# 04_PWMDRIVER.net
KiCad netlist of a schematic drawn in Altium Designer
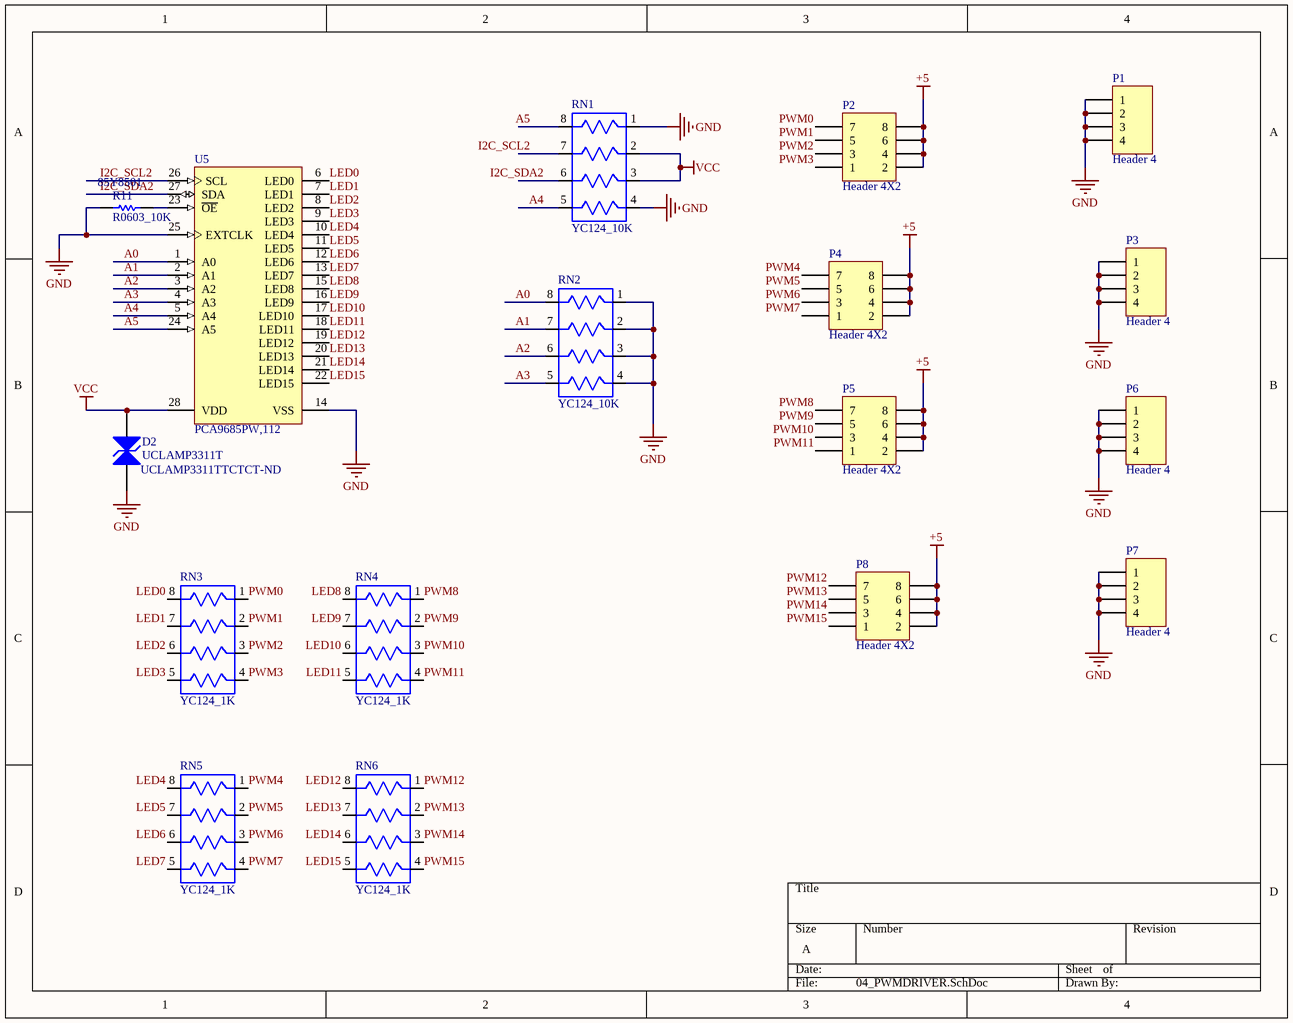
[diagram p0: 04_PWMDRIVER.SchDoc]

(export (version "E")
  (design (tool "Eeschema 10.0.6"))
  (components
    (comp (ref "D2")
      (value "UCLAMP3311T")
      (footprint "SEMT-SLP1006P2-2_V")
      (description "SEMTECH - UCLAMP3311T.TCT - TVS ARRAY, 40W, 3.3V, BI-DIRECTIONAL, SLP1006P2T")
      (fields
        (field (name "SUPPLIER PART NUMBER 1") "UCLAMP3311TTCTCT-ND")
        (field (name "MANUFACTURER") "Semtech")
        (field (name "MANUFACTURER PART NUMBER") "UCLAMP3311T.TCT")
      )
      (libsource (lib "RBS_library") (part "TVS_CLAMP"))
    )
    (comp (ref "P1")
      (value "Header 4")
      (footprint "HDR1X4")
      (description "Header, 4-Pin")
      (fields (field (name "PUBLISHER") "Altium Limited"))
      (libsource (lib "Miscellaneous Connectors") (part "Header 4"))
    )
    (comp (ref "P2")
      (value "Header 4X2")
      (footprint "HDR2X4")
      (description "Header, 4-Pin, Dual row")
      (fields (field (name "PUBLISHER") "Altium Limited"))
      (libsource (lib "Miscellaneous Connectors") (part "Header 4X2"))
    )
    (comp (ref "P3")
      (value "Header 4")
      (footprint "HDR1X4")
      (description "Header, 4-Pin")
      (fields (field (name "PUBLISHER") "Altium Limited"))
      (libsource (lib "Miscellaneous Connectors") (part "Header 4"))
    )
    (comp (ref "P4")
      (value "Header 4X2")
      (footprint "HDR2X4")
      (description "Header, 4-Pin, Dual row")
      (fields (field (name "PUBLISHER") "Altium Limited"))
      (libsource (lib "Miscellaneous Connectors") (part "Header 4X2"))
    )
    (comp (ref "P5")
      (value "Header 4X2")
      (footprint "HDR2X4")
      (description "Header, 4-Pin, Dual row")
      (fields (field (name "PUBLISHER") "Altium Limited"))
      (libsource (lib "Miscellaneous Connectors") (part "Header 4X2"))
    )
    (comp (ref "P6")
      (value "Header 4")
      (footprint "HDR1X4")
      (description "Header, 4-Pin")
      (fields (field (name "PUBLISHER") "Altium Limited"))
      (libsource (lib "Miscellaneous Connectors") (part "Header 4"))
    )
    (comp (ref "P7")
      (value "Header 4")
      (footprint "HDR1X4")
      (description "Header, 4-Pin")
      (fields (field (name "PUBLISHER") "Altium Limited"))
      (libsource (lib "Miscellaneous Connectors") (part "Header 4"))
    )
    (comp (ref "P8")
      (value "Header 4X2")
      (footprint "HDR2X4")
      (description "Header, 4-Pin, Dual row")
      (fields (field (name "PUBLISHER") "Altium Limited"))
      (libsource (lib "Miscellaneous Connectors") (part "Header 4X2"))
    )
    (comp (ref "R11")
      (value "R0603_10K")
      (footprint "RESC1609X55X30LL15T15")
      (description "PANASONIC - ERJ-3EKF1002V. - THICK FILM CHIP RES, 0603, 1%, PRECISION")
      (fields
        (field (name "SUPPLIER PART NUMBER 1") "85Y8501")
        (field (name "MANUFACTURER") "Panasonic")
        (field (name "MANUFACTURER PART NUMBER") "ERJ-3EKF1002V")
      )
      (libsource (lib "RBS_library") (part "R0603"))
    )
    (comp (ref "RN1") (value "YC124_10K") (footprint "YC124") (libsource (lib "RBS_library") (part "YC124")))
    (comp (ref "RN2") (value "YC124_10K") (footprint "YC124") (libsource (lib "RBS_library") (part "YC124")))
    (comp (ref "RN3") (value "YC124_1K") (footprint "YC124") (libsource (lib "RBS_library") (part "YC124")))
    (comp (ref "RN4") (value "YC124_1K") (footprint "YC124") (libsource (lib "RBS_library") (part "YC124")))
    (comp (ref "RN5") (value "YC124_1K") (footprint "YC124") (libsource (lib "RBS_library") (part "YC124")))
    (comp (ref "RN6") (value "YC124_1K") (footprint "YC124") (libsource (lib "RBS_library") (part "YC124")))
    (comp (ref "U5")
      (value "PCA9685PW,112")
      (footprint "SOT361-1_V")
      (fields (field (name "PARTNUMBER") "PCA9685"))
      (libsource (lib "Altium Content Vault") (part "NXP-PCA9685-SOT361-1"))
    )
  )
  (nets
    (net (code "1") (name "+5") (class "Default")
      (node (ref "P2") (pin "2") (pinfunction "2_2") (pintype "passive"))
      (node (ref "P2") (pin "4") (pinfunction "4_4") (pintype "passive"))
      (node (ref "P2") (pin "6") (pinfunction "6_6") (pintype "passive"))
      (node (ref "P2") (pin "8") (pinfunction "8_8") (pintype "passive"))
      (node (ref "P4") (pin "2") (pinfunction "2_2") (pintype "passive"))
      (node (ref "P4") (pin "4") (pinfunction "4_4") (pintype "passive"))
      (node (ref "P4") (pin "6") (pinfunction "6_6") (pintype "passive"))
      (node (ref "P4") (pin "8") (pinfunction "8_8") (pintype "passive"))
      (node (ref "P5") (pin "2") (pinfunction "2_2") (pintype "passive"))
      (node (ref "P5") (pin "4") (pinfunction "4_4") (pintype "passive"))
      (node (ref "P5") (pin "6") (pinfunction "6_6") (pintype "passive"))
      (node (ref "P5") (pin "8") (pinfunction "8_8") (pintype "passive"))
      (node (ref "P8") (pin "2") (pinfunction "2_2") (pintype "passive"))
      (node (ref "P8") (pin "4") (pinfunction "4_4") (pintype "passive"))
      (node (ref "P8") (pin "6") (pinfunction "6_6") (pintype "passive"))
      (node (ref "P8") (pin "8") (pinfunction "8_8") (pintype "passive"))
    )
    (net (code "2") (name "/A0") (class "Default")
      (node (ref "RN2") (pin "8") (pinfunction "8_8") (pintype "passive"))
      (node (ref "U5") (pin "1") (pinfunction "A0_1") (pintype "input"))
    )
    (net (code "3") (name "/A1") (class "Default")
      (node (ref "RN2") (pin "7") (pinfunction "7_7") (pintype "passive"))
      (node (ref "U5") (pin "2") (pinfunction "A1_2") (pintype "input"))
    )
    (net (code "4") (name "/A2") (class "Default")
      (node (ref "RN2") (pin "6") (pinfunction "6_6") (pintype "passive"))
      (node (ref "U5") (pin "3") (pinfunction "A2_3") (pintype "input"))
    )
    (net (code "5") (name "/A3") (class "Default")
      (node (ref "RN2") (pin "5") (pinfunction "5_5") (pintype "passive"))
      (node (ref "U5") (pin "4") (pinfunction "A3_4") (pintype "input"))
    )
    (net (code "6") (name "/A4") (class "Default")
      (node (ref "RN1") (pin "5") (pinfunction "5_5") (pintype "passive"))
      (node (ref "U5") (pin "5") (pinfunction "A4_5") (pintype "input"))
    )
    (net (code "7") (name "/A5") (class "Default")
      (node (ref "RN1") (pin "8") (pinfunction "8_8") (pintype "passive"))
      (node (ref "U5") (pin "24") (pinfunction "A5_24") (pintype "input"))
    )
    (net (code "8") (name "/I2C_SCL2") (class "Default")
      (node (ref "RN1") (pin "7") (pinfunction "7_7") (pintype "passive"))
      (node (ref "U5") (pin "26") (pinfunction "SCL_26") (pintype "input"))
    )
    (net (code "9") (name "/I2C_SDA2") (class "Default")
      (node (ref "RN1") (pin "6") (pinfunction "6_6") (pintype "passive"))
      (node (ref "U5") (pin "27") (pinfunction "SDA_27") (pintype "bidirectional"))
    )
    (net (code "10") (name "/LED0") (class "Default")
      (node (ref "RN3") (pin "8") (pinfunction "8_8") (pintype "passive"))
      (node (ref "U5") (pin "6") (pinfunction "LED0_6") (pintype "tri_state"))
    )
    (net (code "11") (name "/LED1") (class "Default")
      (node (ref "RN3") (pin "7") (pinfunction "7_7") (pintype "passive"))
      (node (ref "U5") (pin "7") (pinfunction "LED1_7") (pintype "tri_state"))
    )
    (net (code "12") (name "/LED2") (class "Default")
      (node (ref "RN3") (pin "6") (pinfunction "6_6") (pintype "passive"))
      (node (ref "U5") (pin "8") (pinfunction "LED2_8") (pintype "tri_state"))
    )
    (net (code "13") (name "/LED3") (class "Default")
      (node (ref "RN3") (pin "5") (pinfunction "5_5") (pintype "passive"))
      (node (ref "U5") (pin "9") (pinfunction "LED3_9") (pintype "tri_state"))
    )
    (net (code "14") (name "/LED4") (class "Default")
      (node (ref "RN5") (pin "8") (pinfunction "8_8") (pintype "passive"))
      (node (ref "U5") (pin "10") (pinfunction "LED4_10") (pintype "tri_state"))
    )
    (net (code "15") (name "/LED5") (class "Default")
      (node (ref "RN5") (pin "7") (pinfunction "7_7") (pintype "passive"))
      (node (ref "U5") (pin "11") (pinfunction "LED5_11") (pintype "tri_state"))
    )
    (net (code "16") (name "/LED6") (class "Default")
      (node (ref "RN5") (pin "6") (pinfunction "6_6") (pintype "passive"))
      (node (ref "U5") (pin "12") (pinfunction "LED6_12") (pintype "tri_state"))
    )
    (net (code "17") (name "/LED7") (class "Default")
      (node (ref "RN5") (pin "5") (pinfunction "5_5") (pintype "passive"))
      (node (ref "U5") (pin "13") (pinfunction "LED7_13") (pintype "tri_state"))
    )
    (net (code "18") (name "/LED8") (class "Default")
      (node (ref "RN4") (pin "8") (pinfunction "8_8") (pintype "passive"))
      (node (ref "U5") (pin "15") (pinfunction "LED8_15") (pintype "tri_state"))
    )
    (net (code "19") (name "/LED9") (class "Default")
      (node (ref "RN4") (pin "7") (pinfunction "7_7") (pintype "passive"))
      (node (ref "U5") (pin "16") (pinfunction "LED9_16") (pintype "tri_state"))
    )
    (net (code "20") (name "/LED10") (class "Default")
      (node (ref "RN4") (pin "6") (pinfunction "6_6") (pintype "passive"))
      (node (ref "U5") (pin "17") (pinfunction "LED10_17") (pintype "tri_state"))
    )
    (net (code "21") (name "/LED11") (class "Default")
      (node (ref "RN4") (pin "5") (pinfunction "5_5") (pintype "passive"))
      (node (ref "U5") (pin "18") (pinfunction "LED11_18") (pintype "tri_state"))
    )
    (net (code "22") (name "/LED12") (class "Default")
      (node (ref "RN6") (pin "8") (pinfunction "8_8") (pintype "passive"))
      (node (ref "U5") (pin "19") (pinfunction "LED12_19") (pintype "tri_state"))
    )
    (net (code "23") (name "/LED13") (class "Default")
      (node (ref "RN6") (pin "7") (pinfunction "7_7") (pintype "passive"))
      (node (ref "U5") (pin "20") (pinfunction "LED13_20") (pintype "tri_state"))
    )
    (net (code "24") (name "/LED14") (class "Default")
      (node (ref "RN6") (pin "6") (pinfunction "6_6") (pintype "passive"))
      (node (ref "U5") (pin "21") (pinfunction "LED14_21") (pintype "tri_state"))
    )
    (net (code "25") (name "/LED15") (class "Default")
      (node (ref "RN6") (pin "5") (pinfunction "5_5") (pintype "passive"))
      (node (ref "U5") (pin "22") (pinfunction "LED15_22") (pintype "tri_state"))
    )
    (net (code "26") (name "/PWM0") (class "Default")
      (node (ref "P2") (pin "7") (pinfunction "7_7") (pintype "passive"))
      (node (ref "RN3") (pin "1") (pinfunction "1_1") (pintype "passive"))
    )
    (net (code "27") (name "/PWM1") (class "Default")
      (node (ref "P2") (pin "5") (pinfunction "5_5") (pintype "passive"))
      (node (ref "RN3") (pin "2") (pinfunction "2_2") (pintype "passive"))
    )
    (net (code "28") (name "/PWM2") (class "Default")
      (node (ref "P2") (pin "3") (pinfunction "3_3") (pintype "passive"))
      (node (ref "RN3") (pin "3") (pinfunction "3_3") (pintype "passive"))
    )
    (net (code "29") (name "/PWM3") (class "Default")
      (node (ref "P2") (pin "1") (pinfunction "1_1") (pintype "passive"))
      (node (ref "RN3") (pin "4") (pinfunction "4_4") (pintype "passive"))
    )
    (net (code "30") (name "/PWM4") (class "Default")
      (node (ref "P4") (pin "7") (pinfunction "7_7") (pintype "passive"))
      (node (ref "RN5") (pin "1") (pinfunction "1_1") (pintype "passive"))
    )
    (net (code "31") (name "/PWM5") (class "Default")
      (node (ref "P4") (pin "5") (pinfunction "5_5") (pintype "passive"))
      (node (ref "RN5") (pin "2") (pinfunction "2_2") (pintype "passive"))
    )
    (net (code "32") (name "/PWM6") (class "Default")
      (node (ref "P4") (pin "3") (pinfunction "3_3") (pintype "passive"))
      (node (ref "RN5") (pin "3") (pinfunction "3_3") (pintype "passive"))
    )
    (net (code "33") (name "/PWM7") (class "Default")
      (node (ref "P4") (pin "1") (pinfunction "1_1") (pintype "passive"))
      (node (ref "RN5") (pin "4") (pinfunction "4_4") (pintype "passive"))
    )
    (net (code "34") (name "/PWM8") (class "Default")
      (node (ref "P5") (pin "7") (pinfunction "7_7") (pintype "passive"))
      (node (ref "RN4") (pin "1") (pinfunction "1_1") (pintype "passive"))
    )
    (net (code "35") (name "/PWM9") (class "Default")
      (node (ref "P5") (pin "5") (pinfunction "5_5") (pintype "passive"))
      (node (ref "RN4") (pin "2") (pinfunction "2_2") (pintype "passive"))
    )
    (net (code "36") (name "/PWM10") (class "Default")
      (node (ref "P5") (pin "3") (pinfunction "3_3") (pintype "passive"))
      (node (ref "RN4") (pin "3") (pinfunction "3_3") (pintype "passive"))
    )
    (net (code "37") (name "/PWM11") (class "Default")
      (node (ref "P5") (pin "1") (pinfunction "1_1") (pintype "passive"))
      (node (ref "RN4") (pin "4") (pinfunction "4_4") (pintype "passive"))
    )
    (net (code "38") (name "/PWM12") (class "Default")
      (node (ref "P8") (pin "7") (pinfunction "7_7") (pintype "passive"))
      (node (ref "RN6") (pin "1") (pinfunction "1_1") (pintype "passive"))
    )
    (net (code "39") (name "/PWM13") (class "Default")
      (node (ref "P8") (pin "5") (pinfunction "5_5") (pintype "passive"))
      (node (ref "RN6") (pin "2") (pinfunction "2_2") (pintype "passive"))
    )
    (net (code "40") (name "/PWM14") (class "Default")
      (node (ref "P8") (pin "3") (pinfunction "3_3") (pintype "passive"))
      (node (ref "RN6") (pin "3") (pinfunction "3_3") (pintype "passive"))
    )
    (net (code "41") (name "/PWM15") (class "Default")
      (node (ref "P8") (pin "1") (pinfunction "1_1") (pintype "passive"))
      (node (ref "RN6") (pin "4") (pinfunction "4_4") (pintype "passive"))
    )
    (net (code "42") (name "GND") (class "Default")
      (node (ref "D2") (pin "1") (pinfunction "A_1") (pintype "passive"))
      (node (ref "P1") (pin "1") (pinfunction "1_1") (pintype "passive"))
      (node (ref "P1") (pin "2") (pinfunction "2_2") (pintype "passive"))
      (node (ref "P1") (pin "3") (pinfunction "3_3") (pintype "passive"))
      (node (ref "P1") (pin "4") (pinfunction "4_4") (pintype "passive"))
      (node (ref "P3") (pin "1") (pinfunction "1_1") (pintype "passive"))
      (node (ref "P3") (pin "2") (pinfunction "2_2") (pintype "passive"))
      (node (ref "P3") (pin "3") (pinfunction "3_3") (pintype "passive"))
      (node (ref "P3") (pin "4") (pinfunction "4_4") (pintype "passive"))
      (node (ref "P6") (pin "1") (pinfunction "1_1") (pintype "passive"))
      (node (ref "P6") (pin "2") (pinfunction "2_2") (pintype "passive"))
      (node (ref "P6") (pin "3") (pinfunction "3_3") (pintype "passive"))
      (node (ref "P6") (pin "4") (pinfunction "4_4") (pintype "passive"))
      (node (ref "P7") (pin "1") (pinfunction "1_1") (pintype "passive"))
      (node (ref "P7") (pin "2") (pinfunction "2_2") (pintype "passive"))
      (node (ref "P7") (pin "3") (pinfunction "3_3") (pintype "passive"))
      (node (ref "P7") (pin "4") (pinfunction "4_4") (pintype "passive"))
      (node (ref "R11") (pin "1") (pinfunction "1_1") (pintype "passive"))
      (node (ref "RN1") (pin "1") (pinfunction "1_1") (pintype "passive"))
      (node (ref "RN1") (pin "4") (pinfunction "4_4") (pintype "passive"))
      (node (ref "RN2") (pin "1") (pinfunction "1_1") (pintype "passive"))
      (node (ref "RN2") (pin "2") (pinfunction "2_2") (pintype "passive"))
      (node (ref "RN2") (pin "3") (pinfunction "3_3") (pintype "passive"))
      (node (ref "RN2") (pin "4") (pinfunction "4_4") (pintype "passive"))
      (node (ref "U5") (pin "14") (pinfunction "VSS_14") (pintype "power_in"))
      (node (ref "U5") (pin "25") (pinfunction "EXTCLK_25") (pintype "input"))
    )
    (net (code "43") (name "Net-(U5-~{OE})") (class "Default")
      (node (ref "R11") (pin "2") (pinfunction "2_2") (pintype "passive"))
      (node (ref "U5") (pin "23") (pinfunction "~{OE}_23") (pintype "input"))
    )
    (net (code "44") (name "VCC") (class "Default")
      (node (ref "D2") (pin "2") (pinfunction "A_2") (pintype "passive"))
      (node (ref "RN1") (pin "2") (pinfunction "2_2") (pintype "passive"))
      (node (ref "RN1") (pin "3") (pinfunction "3_3") (pintype "passive"))
      (node (ref "U5") (pin "28") (pinfunction "VDD_28") (pintype "power_in"))
    )
  )
)
